# lightBoard.net
KiCad netlist of a schematic drawn in EAGLE
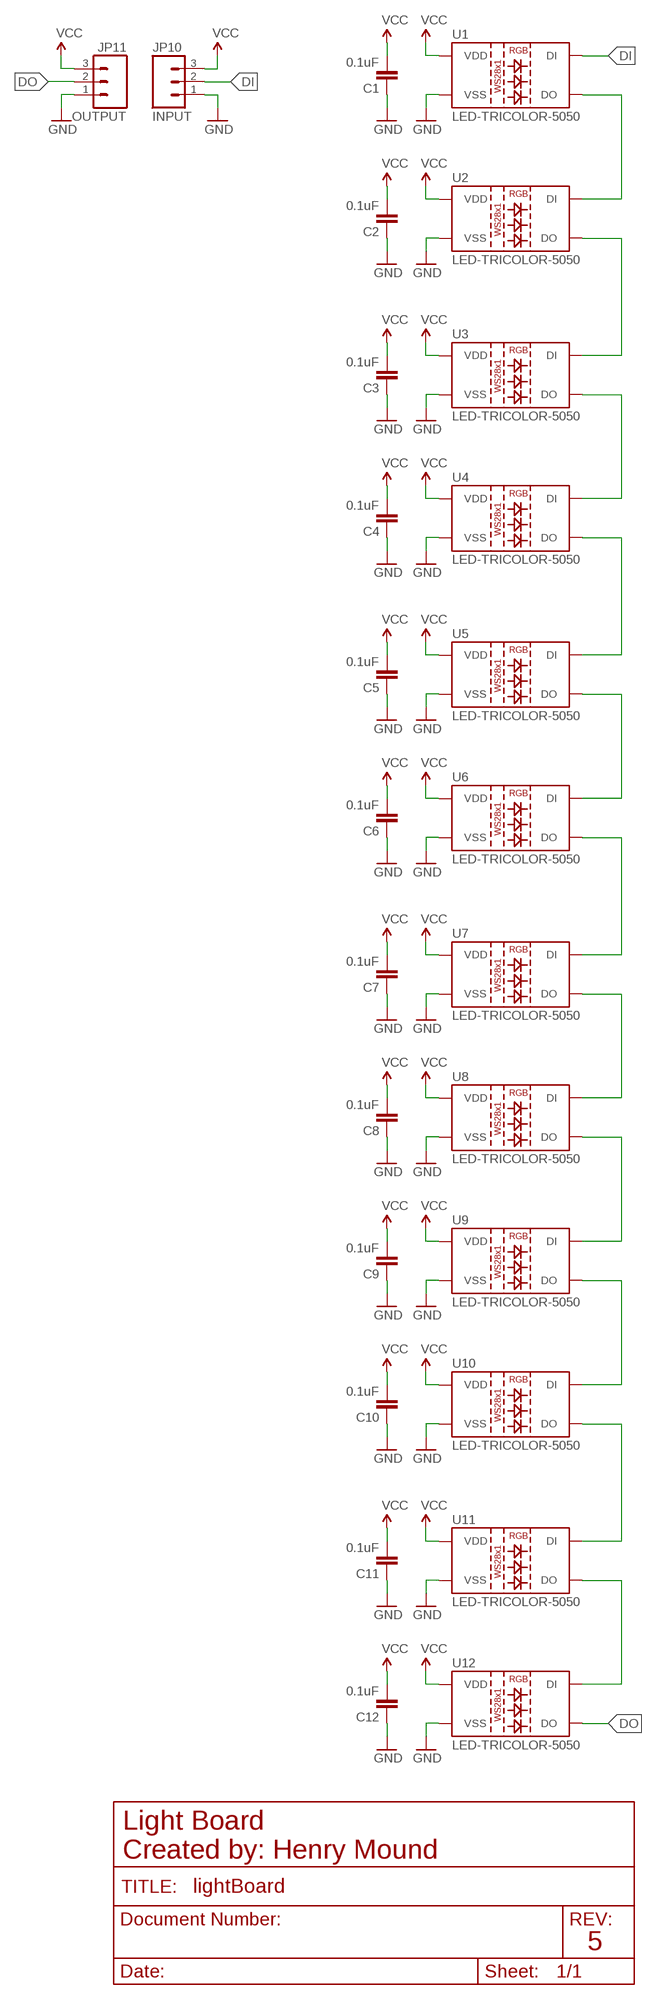
[diagram p0: schematic, sheet 1]

(export (version "E")
  (design (tool "Eeschema 10.0.6"))
  (components
    (comp (ref "C1")
      (value "0.1uF")
      (footprint "eagle-import:0603-CAP")
      (libsource (lib "eagle-import") (part "CAP0603-CAP"))
    )
    (comp (ref "C2")
      (value "0.1uF")
      (footprint "eagle-import:0603-CAP")
      (libsource (lib "eagle-import") (part "CAP0603-CAP"))
    )
    (comp (ref "C3")
      (value "0.1uF")
      (footprint "eagle-import:0603-CAP")
      (libsource (lib "eagle-import") (part "CAP0603-CAP"))
    )
    (comp (ref "C4")
      (value "0.1uF")
      (footprint "eagle-import:0603-CAP")
      (libsource (lib "eagle-import") (part "CAP0603-CAP"))
    )
    (comp (ref "C5")
      (value "0.1uF")
      (footprint "eagle-import:0603-CAP")
      (libsource (lib "eagle-import") (part "CAP0603-CAP"))
    )
    (comp (ref "C6")
      (value "0.1uF")
      (footprint "eagle-import:0603-CAP")
      (libsource (lib "eagle-import") (part "CAP0603-CAP"))
    )
    (comp (ref "C7")
      (value "0.1uF")
      (footprint "eagle-import:0603-CAP")
      (libsource (lib "eagle-import") (part "CAP0603-CAP"))
    )
    (comp (ref "C8")
      (value "0.1uF")
      (footprint "eagle-import:0603-CAP")
      (libsource (lib "eagle-import") (part "CAP0603-CAP"))
    )
    (comp (ref "C9")
      (value "0.1uF")
      (footprint "eagle-import:0603-CAP")
      (libsource (lib "eagle-import") (part "CAP0603-CAP"))
    )
    (comp (ref "C10")
      (value "0.1uF")
      (footprint "eagle-import:0603-CAP")
      (libsource (lib "eagle-import") (part "CAP0603-CAP"))
    )
    (comp (ref "C11")
      (value "0.1uF")
      (footprint "eagle-import:0603-CAP")
      (libsource (lib "eagle-import") (part "CAP0603-CAP"))
    )
    (comp (ref "C12")
      (value "0.1uF")
      (footprint "eagle-import:0603-CAP")
      (libsource (lib "eagle-import") (part "CAP0603-CAP"))
    )
    (comp (ref "JP10")
      (value "INPUT")
      (footprint "eagle-import:1X03")
      (libsource (lib "eagle-import") (part "M03PTH"))
    )
    (comp (ref "JP11")
      (value "OUTPUT")
      (footprint "eagle-import:1X03")
      (libsource (lib "eagle-import") (part "M03PTH"))
    )
    (comp (ref "U1")
      (value "LED-TRICOLOR-5050")
      (footprint "eagle-import:LED-TRICOLOR-5050-IC")
      (libsource (lib "eagle-import") (part "LED-TRICOLOR-5050-ICWS2811"))
    )
    (comp (ref "U2")
      (value "LED-TRICOLOR-5050")
      (footprint "eagle-import:LED-TRICOLOR-5050-IC")
      (libsource (lib "eagle-import") (part "LED-TRICOLOR-5050-ICWS2811"))
    )
    (comp (ref "U3")
      (value "LED-TRICOLOR-5050")
      (footprint "eagle-import:LED-TRICOLOR-5050-IC")
      (libsource (lib "eagle-import") (part "LED-TRICOLOR-5050-ICWS2811"))
    )
    (comp (ref "U4")
      (value "LED-TRICOLOR-5050")
      (footprint "eagle-import:LED-TRICOLOR-5050-IC")
      (libsource (lib "eagle-import") (part "LED-TRICOLOR-5050-ICWS2811"))
    )
    (comp (ref "U5")
      (value "LED-TRICOLOR-5050")
      (footprint "eagle-import:LED-TRICOLOR-5050-IC")
      (libsource (lib "eagle-import") (part "LED-TRICOLOR-5050-ICWS2811"))
    )
    (comp (ref "U6")
      (value "LED-TRICOLOR-5050")
      (footprint "eagle-import:LED-TRICOLOR-5050-IC")
      (libsource (lib "eagle-import") (part "LED-TRICOLOR-5050-ICWS2811"))
    )
    (comp (ref "U7")
      (value "LED-TRICOLOR-5050")
      (footprint "eagle-import:LED-TRICOLOR-5050-IC")
      (libsource (lib "eagle-import") (part "LED-TRICOLOR-5050-ICWS2811"))
    )
    (comp (ref "U8")
      (value "LED-TRICOLOR-5050")
      (footprint "eagle-import:LED-TRICOLOR-5050-IC")
      (libsource (lib "eagle-import") (part "LED-TRICOLOR-5050-ICWS2811"))
    )
    (comp (ref "U9")
      (value "LED-TRICOLOR-5050")
      (footprint "eagle-import:LED-TRICOLOR-5050-IC")
      (libsource (lib "eagle-import") (part "LED-TRICOLOR-5050-ICWS2811"))
    )
    (comp (ref "U10")
      (value "LED-TRICOLOR-5050")
      (footprint "eagle-import:LED-TRICOLOR-5050-IC")
      (libsource (lib "eagle-import") (part "LED-TRICOLOR-5050-ICWS2811"))
    )
    (comp (ref "U11")
      (value "LED-TRICOLOR-5050")
      (footprint "eagle-import:LED-TRICOLOR-5050-IC")
      (libsource (lib "eagle-import") (part "LED-TRICOLOR-5050-ICWS2811"))
    )
    (comp (ref "U12")
      (value "LED-TRICOLOR-5050")
      (footprint "eagle-import:LED-TRICOLOR-5050-IC")
      (libsource (lib "eagle-import") (part "LED-TRICOLOR-5050-ICWS2811"))
    )
  )
  (nets
    (net (code "1") (name "DI") (class "Default")
      (node (ref "JP10") (pin "2") (pinfunction "2_2") (pintype "passive"))
      (node (ref "U1") (pin "2") (pinfunction "DI_2") (pintype "bidirectional"))
    )
    (net (code "2") (name "DO") (class "Default")
      (node (ref "JP11") (pin "2") (pinfunction "2_2") (pintype "passive"))
      (node (ref "U12") (pin "1") (pinfunction "DO_1") (pintype "bidirectional"))
    )
    (net (code "3") (name "GND") (class "Default")
      (node (ref "C1") (pin "1") (pinfunction "1_1") (pintype "passive"))
      (node (ref "C10") (pin "1") (pinfunction "1_1") (pintype "passive"))
      (node (ref "C11") (pin "1") (pinfunction "1_1") (pintype "passive"))
      (node (ref "C12") (pin "1") (pinfunction "1_1") (pintype "passive"))
      (node (ref "C2") (pin "1") (pinfunction "1_1") (pintype "passive"))
      (node (ref "C3") (pin "1") (pinfunction "1_1") (pintype "passive"))
      (node (ref "C4") (pin "1") (pinfunction "1_1") (pintype "passive"))
      (node (ref "C5") (pin "1") (pinfunction "1_1") (pintype "passive"))
      (node (ref "C6") (pin "1") (pinfunction "1_1") (pintype "passive"))
      (node (ref "C7") (pin "1") (pinfunction "1_1") (pintype "passive"))
      (node (ref "C8") (pin "1") (pinfunction "1_1") (pintype "passive"))
      (node (ref "C9") (pin "1") (pinfunction "1_1") (pintype "passive"))
      (node (ref "JP10") (pin "1") (pinfunction "1_1") (pintype "passive"))
      (node (ref "JP11") (pin "1") (pinfunction "1_1") (pintype "passive"))
      (node (ref "U1") (pin "6") (pinfunction "VSS_6") (pintype "bidirectional"))
      (node (ref "U10") (pin "6") (pinfunction "VSS_6") (pintype "bidirectional"))
      (node (ref "U11") (pin "6") (pinfunction "VSS_6") (pintype "bidirectional"))
      (node (ref "U12") (pin "6") (pinfunction "VSS_6") (pintype "bidirectional"))
      (node (ref "U2") (pin "6") (pinfunction "VSS_6") (pintype "bidirectional"))
      (node (ref "U3") (pin "6") (pinfunction "VSS_6") (pintype "bidirectional"))
      (node (ref "U4") (pin "6") (pinfunction "VSS_6") (pintype "bidirectional"))
      (node (ref "U5") (pin "6") (pinfunction "VSS_6") (pintype "bidirectional"))
      (node (ref "U6") (pin "6") (pinfunction "VSS_6") (pintype "bidirectional"))
      (node (ref "U7") (pin "6") (pinfunction "VSS_6") (pintype "bidirectional"))
      (node (ref "U8") (pin "6") (pinfunction "VSS_6") (pintype "bidirectional"))
      (node (ref "U9") (pin "6") (pinfunction "VSS_6") (pintype "bidirectional"))
    )
    (net (code "4") (name "Net-(U1-DO)") (class "Default")
      (node (ref "U1") (pin "1") (pinfunction "DO_1") (pintype "bidirectional"))
      (node (ref "U2") (pin "2") (pinfunction "DI_2") (pintype "bidirectional"))
    )
    (net (code "5") (name "Net-(U2-DO)") (class "Default")
      (node (ref "U2") (pin "1") (pinfunction "DO_1") (pintype "bidirectional"))
      (node (ref "U3") (pin "2") (pinfunction "DI_2") (pintype "bidirectional"))
    )
    (net (code "6") (name "Net-(U3-DO)") (class "Default")
      (node (ref "U3") (pin "1") (pinfunction "DO_1") (pintype "bidirectional"))
      (node (ref "U4") (pin "2") (pinfunction "DI_2") (pintype "bidirectional"))
    )
    (net (code "7") (name "Net-(U4-DO)") (class "Default")
      (node (ref "U4") (pin "1") (pinfunction "DO_1") (pintype "bidirectional"))
      (node (ref "U5") (pin "2") (pinfunction "DI_2") (pintype "bidirectional"))
    )
    (net (code "8") (name "Net-(U5-DO)") (class "Default")
      (node (ref "U5") (pin "1") (pinfunction "DO_1") (pintype "bidirectional"))
      (node (ref "U6") (pin "2") (pinfunction "DI_2") (pintype "bidirectional"))
    )
    (net (code "9") (name "Net-(U6-DO)") (class "Default")
      (node (ref "U6") (pin "1") (pinfunction "DO_1") (pintype "bidirectional"))
      (node (ref "U7") (pin "2") (pinfunction "DI_2") (pintype "bidirectional"))
    )
    (net (code "10") (name "Net-(U7-DO)") (class "Default")
      (node (ref "U7") (pin "1") (pinfunction "DO_1") (pintype "bidirectional"))
      (node (ref "U8") (pin "2") (pinfunction "DI_2") (pintype "bidirectional"))
    )
    (net (code "11") (name "Net-(U8-DO)") (class "Default")
      (node (ref "U8") (pin "1") (pinfunction "DO_1") (pintype "bidirectional"))
      (node (ref "U9") (pin "2") (pinfunction "DI_2") (pintype "bidirectional"))
    )
    (net (code "12") (name "Net-(U10-DI)") (class "Default")
      (node (ref "U10") (pin "2") (pinfunction "DI_2") (pintype "bidirectional"))
      (node (ref "U9") (pin "1") (pinfunction "DO_1") (pintype "bidirectional"))
    )
    (net (code "13") (name "Net-(U10-DO)") (class "Default")
      (node (ref "U10") (pin "1") (pinfunction "DO_1") (pintype "bidirectional"))
      (node (ref "U11") (pin "2") (pinfunction "DI_2") (pintype "bidirectional"))
    )
    (net (code "14") (name "Net-(U11-DO)") (class "Default")
      (node (ref "U11") (pin "1") (pinfunction "DO_1") (pintype "bidirectional"))
      (node (ref "U12") (pin "2") (pinfunction "DI_2") (pintype "bidirectional"))
    )
    (net (code "15") (name "VCC") (class "Default")
      (node (ref "C1") (pin "2") (pinfunction "2_2") (pintype "passive"))
      (node (ref "C10") (pin "2") (pinfunction "2_2") (pintype "passive"))
      (node (ref "C11") (pin "2") (pinfunction "2_2") (pintype "passive"))
      (node (ref "C12") (pin "2") (pinfunction "2_2") (pintype "passive"))
      (node (ref "C2") (pin "2") (pinfunction "2_2") (pintype "passive"))
      (node (ref "C3") (pin "2") (pinfunction "2_2") (pintype "passive"))
      (node (ref "C4") (pin "2") (pinfunction "2_2") (pintype "passive"))
      (node (ref "C5") (pin "2") (pinfunction "2_2") (pintype "passive"))
      (node (ref "C6") (pin "2") (pinfunction "2_2") (pintype "passive"))
      (node (ref "C7") (pin "2") (pinfunction "2_2") (pintype "passive"))
      (node (ref "C8") (pin "2") (pinfunction "2_2") (pintype "passive"))
      (node (ref "C9") (pin "2") (pinfunction "2_2") (pintype "passive"))
      (node (ref "JP10") (pin "3") (pinfunction "3_3") (pintype "passive"))
      (node (ref "JP11") (pin "3") (pinfunction "3_3") (pintype "passive"))
      (node (ref "U1") (pin "3") (pinfunction "VDD_3") (pintype "bidirectional"))
      (node (ref "U1") (pin "5") (pinfunction "VDD_5") (pintype "bidirectional"))
      (node (ref "U10") (pin "3") (pinfunction "VDD_3") (pintype "bidirectional"))
      (node (ref "U10") (pin "5") (pinfunction "VDD_5") (pintype "bidirectional"))
      (node (ref "U11") (pin "3") (pinfunction "VDD_3") (pintype "bidirectional"))
      (node (ref "U11") (pin "5") (pinfunction "VDD_5") (pintype "bidirectional"))
      (node (ref "U12") (pin "3") (pinfunction "VDD_3") (pintype "bidirectional"))
      (node (ref "U12") (pin "5") (pinfunction "VDD_5") (pintype "bidirectional"))
      (node (ref "U2") (pin "3") (pinfunction "VDD_3") (pintype "bidirectional"))
      (node (ref "U2") (pin "5") (pinfunction "VDD_5") (pintype "bidirectional"))
      (node (ref "U3") (pin "3") (pinfunction "VDD_3") (pintype "bidirectional"))
      (node (ref "U3") (pin "5") (pinfunction "VDD_5") (pintype "bidirectional"))
      (node (ref "U4") (pin "3") (pinfunction "VDD_3") (pintype "bidirectional"))
      (node (ref "U4") (pin "5") (pinfunction "VDD_5") (pintype "bidirectional"))
      (node (ref "U5") (pin "3") (pinfunction "VDD_3") (pintype "bidirectional"))
      (node (ref "U5") (pin "5") (pinfunction "VDD_5") (pintype "bidirectional"))
      (node (ref "U6") (pin "3") (pinfunction "VDD_3") (pintype "bidirectional"))
      (node (ref "U6") (pin "5") (pinfunction "VDD_5") (pintype "bidirectional"))
      (node (ref "U7") (pin "3") (pinfunction "VDD_3") (pintype "bidirectional"))
      (node (ref "U7") (pin "5") (pinfunction "VDD_5") (pintype "bidirectional"))
      (node (ref "U8") (pin "3") (pinfunction "VDD_3") (pintype "bidirectional"))
      (node (ref "U8") (pin "5") (pinfunction "VDD_5") (pintype "bidirectional"))
      (node (ref "U9") (pin "3") (pinfunction "VDD_3") (pintype "bidirectional"))
      (node (ref "U9") (pin "5") (pinfunction "VDD_5") (pintype "bidirectional"))
    )
  )
)
